# Multiplexer.net
KiCad netlist of a schematic drawn in Altium Designer
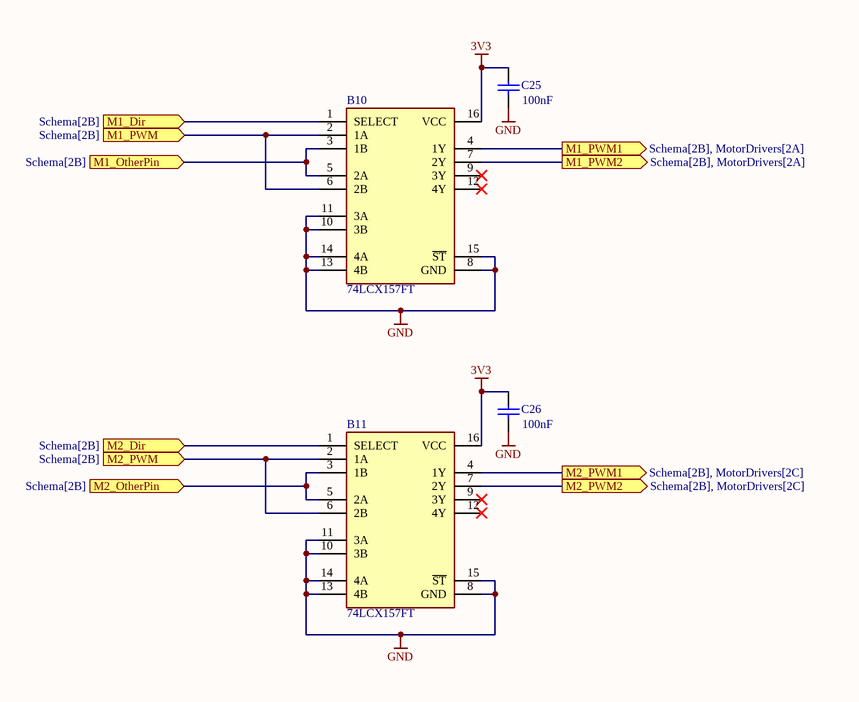
[diagram p0: Multiplexer.SchDoc]

(export (version "E")
  (design (tool "Eeschema 10.0.6"))
  (components
    (comp (ref "B10")
      (value "74LCX157FT")
      (footprint "SOP65P640X120-16M")
      (description "74LCX157FT Toshiba, Multiplexer Quad, -0.5  6.5 V, 16-Pin TSSOP")
      (fields (field (name "MOUSER PART NUMBER") "757-74LCX157FT"))
      (libsource (lib "SchematicLib") (part "74LCX157FT"))
    )
    (comp (ref "B11")
      (value "74LCX157FT")
      (footprint "SOP65P640X120-16M")
      (description "74LCX157FT Toshiba, Multiplexer Quad, -0.5  6.5 V, 16-Pin TSSOP")
      (fields (field (name "MOUSER PART NUMBER") "757-74LCX157FT"))
      (libsource (lib "SchematicLib") (part "74LCX157FT"))
    )
    (comp (ref "C25")
      (value "100nF")
      (footprint "0805_Lorin")
      (description "Capacitor")
      (fields (field (name "Comment") "Cap") (field (name "PUBLISHER") "Altium Limited"))
      (libsource (lib "Miscellaneous Devices") (part "Cap"))
    )
    (comp (ref "C26")
      (value "100nF")
      (footprint "0805_Lorin")
      (description "Capacitor")
      (fields (field (name "Comment") "Cap") (field (name "PUBLISHER") "Altium Limited"))
      (libsource (lib "Miscellaneous Devices") (part "Cap"))
    )
  )
  (nets
    (net (code "1") (name "/M1_Dir") (class "Default")
      (node (ref "B10") (pin "1") (pinfunction "SELECT_1") (pintype "passive"))
    )
    (net (code "2") (name "/M1_OtherPin") (class "Default")
      (node (ref "B10") (pin "3") (pinfunction "1B_3") (pintype "passive"))
      (node (ref "B10") (pin "5") (pinfunction "2A_5") (pintype "passive"))
    )
    (net (code "3") (name "/M1_PWM") (class "Default")
      (node (ref "B10") (pin "2") (pinfunction "1A_2") (pintype "passive"))
      (node (ref "B10") (pin "6") (pinfunction "2B_6") (pintype "passive"))
    )
    (net (code "4") (name "/M1_PWM1") (class "Default")
      (node (ref "B10") (pin "4") (pinfunction "1Y_4") (pintype "passive"))
    )
    (net (code "5") (name "/M1_PWM2") (class "Default")
      (node (ref "B10") (pin "7") (pinfunction "2Y_7") (pintype "passive"))
    )
    (net (code "6") (name "/M2_Dir") (class "Default")
      (node (ref "B11") (pin "1") (pinfunction "SELECT_1") (pintype "passive"))
    )
    (net (code "7") (name "/M2_OtherPin") (class "Default")
      (node (ref "B11") (pin "3") (pinfunction "1B_3") (pintype "passive"))
      (node (ref "B11") (pin "5") (pinfunction "2A_5") (pintype "passive"))
    )
    (net (code "8") (name "/M2_PWM") (class "Default")
      (node (ref "B11") (pin "2") (pinfunction "1A_2") (pintype "passive"))
      (node (ref "B11") (pin "6") (pinfunction "2B_6") (pintype "passive"))
    )
    (net (code "9") (name "/M2_PWM1") (class "Default")
      (node (ref "B11") (pin "4") (pinfunction "1Y_4") (pintype "passive"))
    )
    (net (code "10") (name "/M2_PWM2") (class "Default")
      (node (ref "B11") (pin "7") (pinfunction "2Y_7") (pintype "passive"))
    )
    (net (code "11") (name "3V3") (class "Default")
      (node (ref "B10") (pin "16") (pinfunction "VCC_16") (pintype "passive"))
      (node (ref "B11") (pin "16") (pinfunction "VCC_16") (pintype "passive"))
      (node (ref "C25") (pin "1") (pinfunction "1_1") (pintype "passive"))
      (node (ref "C26") (pin "1") (pinfunction "1_1") (pintype "passive"))
    )
    (net (code "12") (name "GND") (class "Default")
      (node (ref "B10") (pin "10") (pinfunction "3B_10") (pintype "passive"))
      (node (ref "B10") (pin "11") (pinfunction "3A_11") (pintype "passive"))
      (node (ref "B10") (pin "13") (pinfunction "4B_13") (pintype "passive"))
      (node (ref "B10") (pin "14") (pinfunction "4A_14") (pintype "passive"))
      (node (ref "B10") (pin "15") (pinfunction "~{ST}_15") (pintype "passive"))
      (node (ref "B10") (pin "8") (pinfunction "GND_8") (pintype "passive"))
      (node (ref "B11") (pin "10") (pinfunction "3B_10") (pintype "passive"))
      (node (ref "B11") (pin "11") (pinfunction "3A_11") (pintype "passive"))
      (node (ref "B11") (pin "13") (pinfunction "4B_13") (pintype "passive"))
      (node (ref "B11") (pin "14") (pinfunction "4A_14") (pintype "passive"))
      (node (ref "B11") (pin "15") (pinfunction "~{ST}_15") (pintype "passive"))
      (node (ref "B11") (pin "8") (pinfunction "GND_8") (pintype "passive"))
      (node (ref "C25") (pin "2") (pinfunction "2_2") (pintype "passive"))
      (node (ref "C26") (pin "2") (pinfunction "2_2") (pintype "passive"))
    )
    (net (code "13") (name "unconnected-(B10-3Y-Pad9)") (class "Default")
      (node (ref "B10") (pin "9") (pinfunction "3Y_9") (pintype "passive+no_connect"))
    )
    (net (code "14") (name "unconnected-(B10-4Y-Pad12)") (class "Default")
      (node (ref "B10") (pin "12") (pinfunction "4Y_12") (pintype "passive+no_connect"))
    )
    (net (code "15") (name "unconnected-(B11-3Y-Pad9)") (class "Default")
      (node (ref "B11") (pin "9") (pinfunction "3Y_9") (pintype "passive+no_connect"))
    )
    (net (code "16") (name "unconnected-(B11-4Y-Pad12)") (class "Default")
      (node (ref "B11") (pin "12") (pinfunction "4Y_12") (pintype "passive+no_connect"))
    )
  )
)
